# Sheet3.net
KiCad netlist of a schematic drawn in Altium Designer
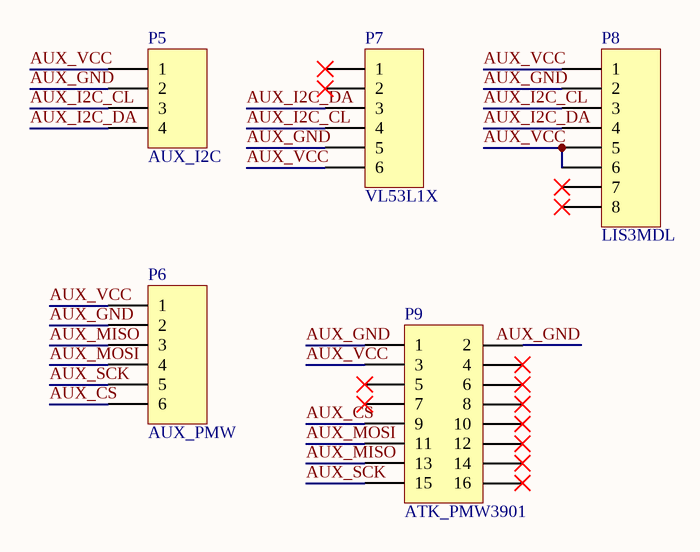
[diagram p0: Sheet3.SchDoc]

(export (version "E")
  (design (tool "Eeschema 10.0.6"))
  (components
    (comp (ref "P5")
      (value "AUX_I2C")
      (footprint "XH2.54-4P")
      (description "Header, 4-Pin")
      (fields (field (name "PUBLISHER") "Altium Limited"))
      (libsource (lib "Miscellaneous Connectors") (part "Header 4"))
    )
    (comp (ref "P6")
      (value "AUX_PMW")
      (footprint "XH2.54-6P")
      (description "Header, 6-Pin")
      (fields (field (name "PUBLISHER") "Altium Limited"))
      (libsource (lib "Miscellaneous Connectors") (part "Header 6"))
    )
    (comp (ref "P7")
      (value "VL53L1X")
      (footprint "HDR1X6")
      (description "Header, 6-Pin")
      (fields (field (name "PUBLISHER") "Altium Limited"))
      (libsource (lib "Miscellaneous Connectors") (part "Header 6"))
    )
    (comp (ref "P8")
      (value "LIS3MDL")
      (footprint "HDR1X8")
      (description "Header, 8-Pin")
      (fields (field (name "PUBLISHER") "Altium Limited"))
      (libsource (lib "Miscellaneous Connectors") (part "Header 8"))
    )
    (comp (ref "P9")
      (value "ATK_PMW3901")
      (footprint "ATK-PMW3901")
      (description "Header, 8-Pin, Dual row")
      (fields (field (name "PUBLISHER") "Altium Limited"))
      (libsource (lib "Miscellaneous Connectors") (part "Header 8X2"))
    )
  )
  (nets
    (net (code "1") (name "/AUX_CS") (class "Default")
      (node (ref "P6") (pin "6") (pinfunction "6_6") (pintype "passive"))
      (node (ref "P9") (pin "9") (pinfunction "9_9") (pintype "passive"))
    )
    (net (code "2") (name "/AUX_GND") (class "Default")
      (node (ref "P5") (pin "2") (pinfunction "2_2") (pintype "passive"))
      (node (ref "P6") (pin "2") (pinfunction "2_2") (pintype "passive"))
      (node (ref "P7") (pin "5") (pinfunction "5_5") (pintype "passive"))
      (node (ref "P8") (pin "2") (pinfunction "2_2") (pintype "passive"))
      (node (ref "P9") (pin "1") (pinfunction "1_1") (pintype "passive"))
      (node (ref "P9") (pin "2") (pinfunction "2_2") (pintype "passive"))
    )
    (net (code "3") (name "/AUX_I2C_CL") (class "Default")
      (node (ref "P5") (pin "3") (pinfunction "3_3") (pintype "passive"))
      (node (ref "P7") (pin "4") (pinfunction "4_4") (pintype "passive"))
      (node (ref "P8") (pin "3") (pinfunction "3_3") (pintype "passive"))
    )
    (net (code "4") (name "/AUX_I2C_DA") (class "Default")
      (node (ref "P5") (pin "4") (pinfunction "4_4") (pintype "passive"))
      (node (ref "P7") (pin "3") (pinfunction "3_3") (pintype "passive"))
      (node (ref "P8") (pin "4") (pinfunction "4_4") (pintype "passive"))
    )
    (net (code "5") (name "/AUX_MISO") (class "Default")
      (node (ref "P6") (pin "3") (pinfunction "3_3") (pintype "passive"))
      (node (ref "P9") (pin "13") (pinfunction "13_13") (pintype "passive"))
    )
    (net (code "6") (name "/AUX_MOSI") (class "Default")
      (node (ref "P6") (pin "4") (pinfunction "4_4") (pintype "passive"))
      (node (ref "P9") (pin "11") (pinfunction "11_11") (pintype "passive"))
    )
    (net (code "7") (name "/AUX_SCK") (class "Default")
      (node (ref "P6") (pin "5") (pinfunction "5_5") (pintype "passive"))
      (node (ref "P9") (pin "15") (pinfunction "15_15") (pintype "passive"))
    )
    (net (code "8") (name "/AUX_VCC") (class "Default")
      (node (ref "P5") (pin "1") (pinfunction "1_1") (pintype "passive"))
      (node (ref "P6") (pin "1") (pinfunction "1_1") (pintype "passive"))
      (node (ref "P7") (pin "6") (pinfunction "6_6") (pintype "passive"))
      (node (ref "P8") (pin "1") (pinfunction "1_1") (pintype "passive"))
      (node (ref "P8") (pin "5") (pinfunction "5_5") (pintype "passive"))
      (node (ref "P8") (pin "6") (pinfunction "6_6") (pintype "passive"))
      (node (ref "P9") (pin "3") (pinfunction "3_3") (pintype "passive"))
    )
    (net (code "9") (name "unconnected-(P7-Pad1)") (class "Default")
      (node (ref "P7") (pin "1") (pinfunction "1_1") (pintype "passive+no_connect"))
    )
    (net (code "10") (name "unconnected-(P7-Pad2)") (class "Default")
      (node (ref "P7") (pin "2") (pinfunction "2_2") (pintype "passive+no_connect"))
    )
    (net (code "11") (name "unconnected-(P8-Pad7)") (class "Default")
      (node (ref "P8") (pin "7") (pinfunction "7_7") (pintype "passive+no_connect"))
    )
    (net (code "12") (name "unconnected-(P8-Pad8)") (class "Default")
      (node (ref "P8") (pin "8") (pinfunction "8_8") (pintype "passive+no_connect"))
    )
    (net (code "13") (name "unconnected-(P9-Pad4)") (class "Default")
      (node (ref "P9") (pin "4") (pinfunction "4_4") (pintype "passive+no_connect"))
    )
    (net (code "14") (name "unconnected-(P9-Pad5)") (class "Default")
      (node (ref "P9") (pin "5") (pinfunction "5_5") (pintype "passive+no_connect"))
    )
    (net (code "15") (name "unconnected-(P9-Pad6)") (class "Default")
      (node (ref "P9") (pin "6") (pinfunction "6_6") (pintype "passive+no_connect"))
    )
    (net (code "16") (name "unconnected-(P9-Pad7)") (class "Default")
      (node (ref "P9") (pin "7") (pinfunction "7_7") (pintype "passive+no_connect"))
    )
    (net (code "17") (name "unconnected-(P9-Pad8)") (class "Default")
      (node (ref "P9") (pin "8") (pinfunction "8_8") (pintype "passive+no_connect"))
    )
    (net (code "18") (name "unconnected-(P9-Pad10)") (class "Default")
      (node (ref "P9") (pin "10") (pinfunction "10_10") (pintype "passive+no_connect"))
    )
    (net (code "19") (name "unconnected-(P9-Pad12)") (class "Default")
      (node (ref "P9") (pin "12") (pinfunction "12_12") (pintype "passive+no_connect"))
    )
    (net (code "20") (name "unconnected-(P9-Pad14)") (class "Default")
      (node (ref "P9") (pin "14") (pinfunction "14_14") (pintype "passive+no_connect"))
    )
    (net (code "21") (name "unconnected-(P9-Pad16)") (class "Default")
      (node (ref "P9") (pin "16") (pinfunction "16_16") (pintype "passive+no_connect"))
    )
  )
)
